# H07R1x_Frontend.net
KiCad netlist of a schematic drawn in Altium Designer
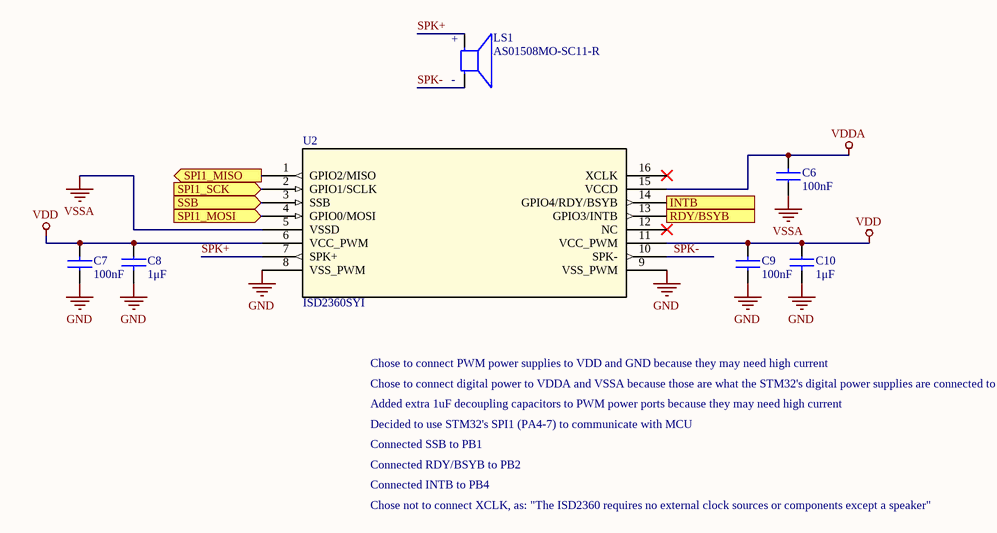
[diagram p0: H07R1x_Frontend.SchDoc]

(export (version "E")
  (design (tool "Eeschema 10.0.6"))
  (components
    (comp (ref "C6")
      (value "100nF")
      (footprint "C0603")
      (fields
        (field (name "MANUFACTURER") "Samsung Electro-Mechanics")
        (field (name "MANUFACTURER PART NUMBER") "CL10B104KA8NNNC")
        (field (name "TOLERANCE") "10%")
      )
      (libsource (lib "Hexabitz Altium Library") (part "generic Capacitor"))
    )
    (comp (ref "C7")
      (value "100nF")
      (footprint "C0603")
      (fields
        (field (name "MANUFACTURER") "Samsung Electro-Mechanics")
        (field (name "MANUFACTURER PART NUMBER") "CL10B104KA8NNNC")
        (field (name "TOLERANCE") "10%")
      )
      (libsource (lib "Hexabitz Altium Library") (part "generic Capacitor"))
    )
    (comp (ref "C8")
      (value "1μF")
      (footprint "C0805")
      (fields
        (field (name "MANUFACTURER") "Samsung Electro-Mechanics")
        (field (name "MANUFACTURER PART NUMBER") "CL21X475KAQNNNE")
        (field (name "TOLERANCE") "10%")
      )
      (libsource (lib "Hexabitz Altium Library") (part "generic Capacitor"))
    )
    (comp (ref "C9")
      (value "100nF")
      (footprint "C0603")
      (fields
        (field (name "MANUFACTURER") "Samsung Electro-Mechanics")
        (field (name "MANUFACTURER PART NUMBER") "CL10B104KA8NNNC")
        (field (name "TOLERANCE") "10%")
      )
      (libsource (lib "Hexabitz Altium Library") (part "generic Capacitor"))
    )
    (comp (ref "C10")
      (value "1μF")
      (footprint "C0805")
      (fields
        (field (name "MANUFACTURER") "Samsung Electro-Mechanics")
        (field (name "MANUFACTURER PART NUMBER") "CL21X475KAQNNNE")
        (field (name "TOLERANCE") "10%")
      )
      (libsource (lib "Hexabitz Altium Library") (part "generic Capacitor"))
    )
    (comp (ref "LS1")
      (value "AS01508MO-SC11-R")
      (footprint "SPKR_AS01508MO-SC11-R")
      (libsource (lib "AS01508MO-SC11-R") (part "AS01508MO-SC11-R"))
    )
    (comp (ref "U2")
      (value "ISD2360SYI")
      (footprint "ISD2360SYI_NUV")
      (description "Description")
      (fields (field (name "COPYRIGHT") "Copyright (C) 2025 Ultra Librarian. All rights reserved."))
      (libsource (lib "ISD2360SYI") (part "ISD2360SYI"))
    )
  )
  (nets
    (net (code "1") (name "/INTB") (class "Default")
      (node (ref "U2") (pin "14") (pinfunction "GPIO4/RDY/BSYB_14") (pintype "output"))
    )
    (net (code "2") (name "/RDY{slash}BSYB") (class "Default")
      (node (ref "U2") (pin "13") (pinfunction "GPIO3/INTB_13") (pintype "output"))
    )
    (net (code "3") (name "/SPI1_MISO") (class "Default")
      (node (ref "U2") (pin "1") (pinfunction "GPIO2/MISO_1") (pintype "output"))
    )
    (net (code "4") (name "/SPI1_MOSI") (class "Default")
      (node (ref "U2") (pin "4") (pinfunction "GPIO0/MOSI_4") (pintype "input"))
    )
    (net (code "5") (name "/SPI1_SCK") (class "Default")
      (node (ref "U2") (pin "2") (pinfunction "GPIO1/SCLK_2") (pintype "input"))
    )
    (net (code "6") (name "/SPK+") (class "Default")
      (node (ref "LS1") (pin "P") (pinfunction "P_P") (pintype "passive"))
      (node (ref "U2") (pin "7") (pinfunction "SPK+_7") (pintype "output"))
    )
    (net (code "7") (name "/SPK-") (class "Default")
      (node (ref "LS1") (pin "N") (pinfunction "N_N") (pintype "passive"))
      (node (ref "U2") (pin "10") (pinfunction "SPK-_10") (pintype "output"))
    )
    (net (code "8") (name "/SSB") (class "Default")
      (node (ref "U2") (pin "3") (pinfunction "SSB_3") (pintype "input"))
    )
    (net (code "9") (name "GND") (class "Default")
      (node (ref "C10") (pin "2") (pinfunction "2_2") (pintype "passive"))
      (node (ref "C7") (pin "1") (pinfunction "1_1") (pintype "passive"))
      (node (ref "C8") (pin "2") (pinfunction "2_2") (pintype "passive"))
      (node (ref "C9") (pin "1") (pinfunction "1_1") (pintype "passive"))
      (node (ref "U2") (pin "8") (pinfunction "VSS_PWM_8") (pintype "power_in"))
      (node (ref "U2") (pin "9") (pinfunction "VSS_PWM_9") (pintype "power_in"))
    )
    (net (code "10") (name "VDD") (class "Default")
      (node (ref "C10") (pin "1") (pinfunction "1_1") (pintype "passive"))
      (node (ref "C7") (pin "2") (pinfunction "2_2") (pintype "passive"))
      (node (ref "C8") (pin "1") (pinfunction "1_1") (pintype "passive"))
      (node (ref "C9") (pin "2") (pinfunction "2_2") (pintype "passive"))
      (node (ref "U2") (pin "11") (pinfunction "VCC_PWM_11") (pintype "power_in"))
      (node (ref "U2") (pin "6") (pinfunction "VCC_PWM_6") (pintype "power_in"))
    )
    (net (code "11") (name "VDDA") (class "Default")
      (node (ref "C6") (pin "2") (pinfunction "2_2") (pintype "passive"))
      (node (ref "U2") (pin "15") (pinfunction "VCCD_15") (pintype "power_in"))
    )
    (net (code "12") (name "VSSA") (class "Default")
      (node (ref "C6") (pin "1") (pinfunction "1_1") (pintype "passive"))
      (node (ref "U2") (pin "5") (pinfunction "VSSD_5") (pintype "power_in"))
    )
    (net (code "13") (name "unconnected-(U2-NC-Pad12)") (class "Default")
      (node (ref "U2") (pin "12") (pinfunction "NC_12") (pintype "passive+no_connect"))
    )
    (net (code "14") (name "unconnected-(U2-XCLK-Pad16)") (class "Default")
      (node (ref "U2") (pin "16") (pinfunction "XCLK_16") (pintype "passive+no_connect"))
    )
  )
)
